# IOBR.net
KiCad netlist of a schematic drawn in EAGLE
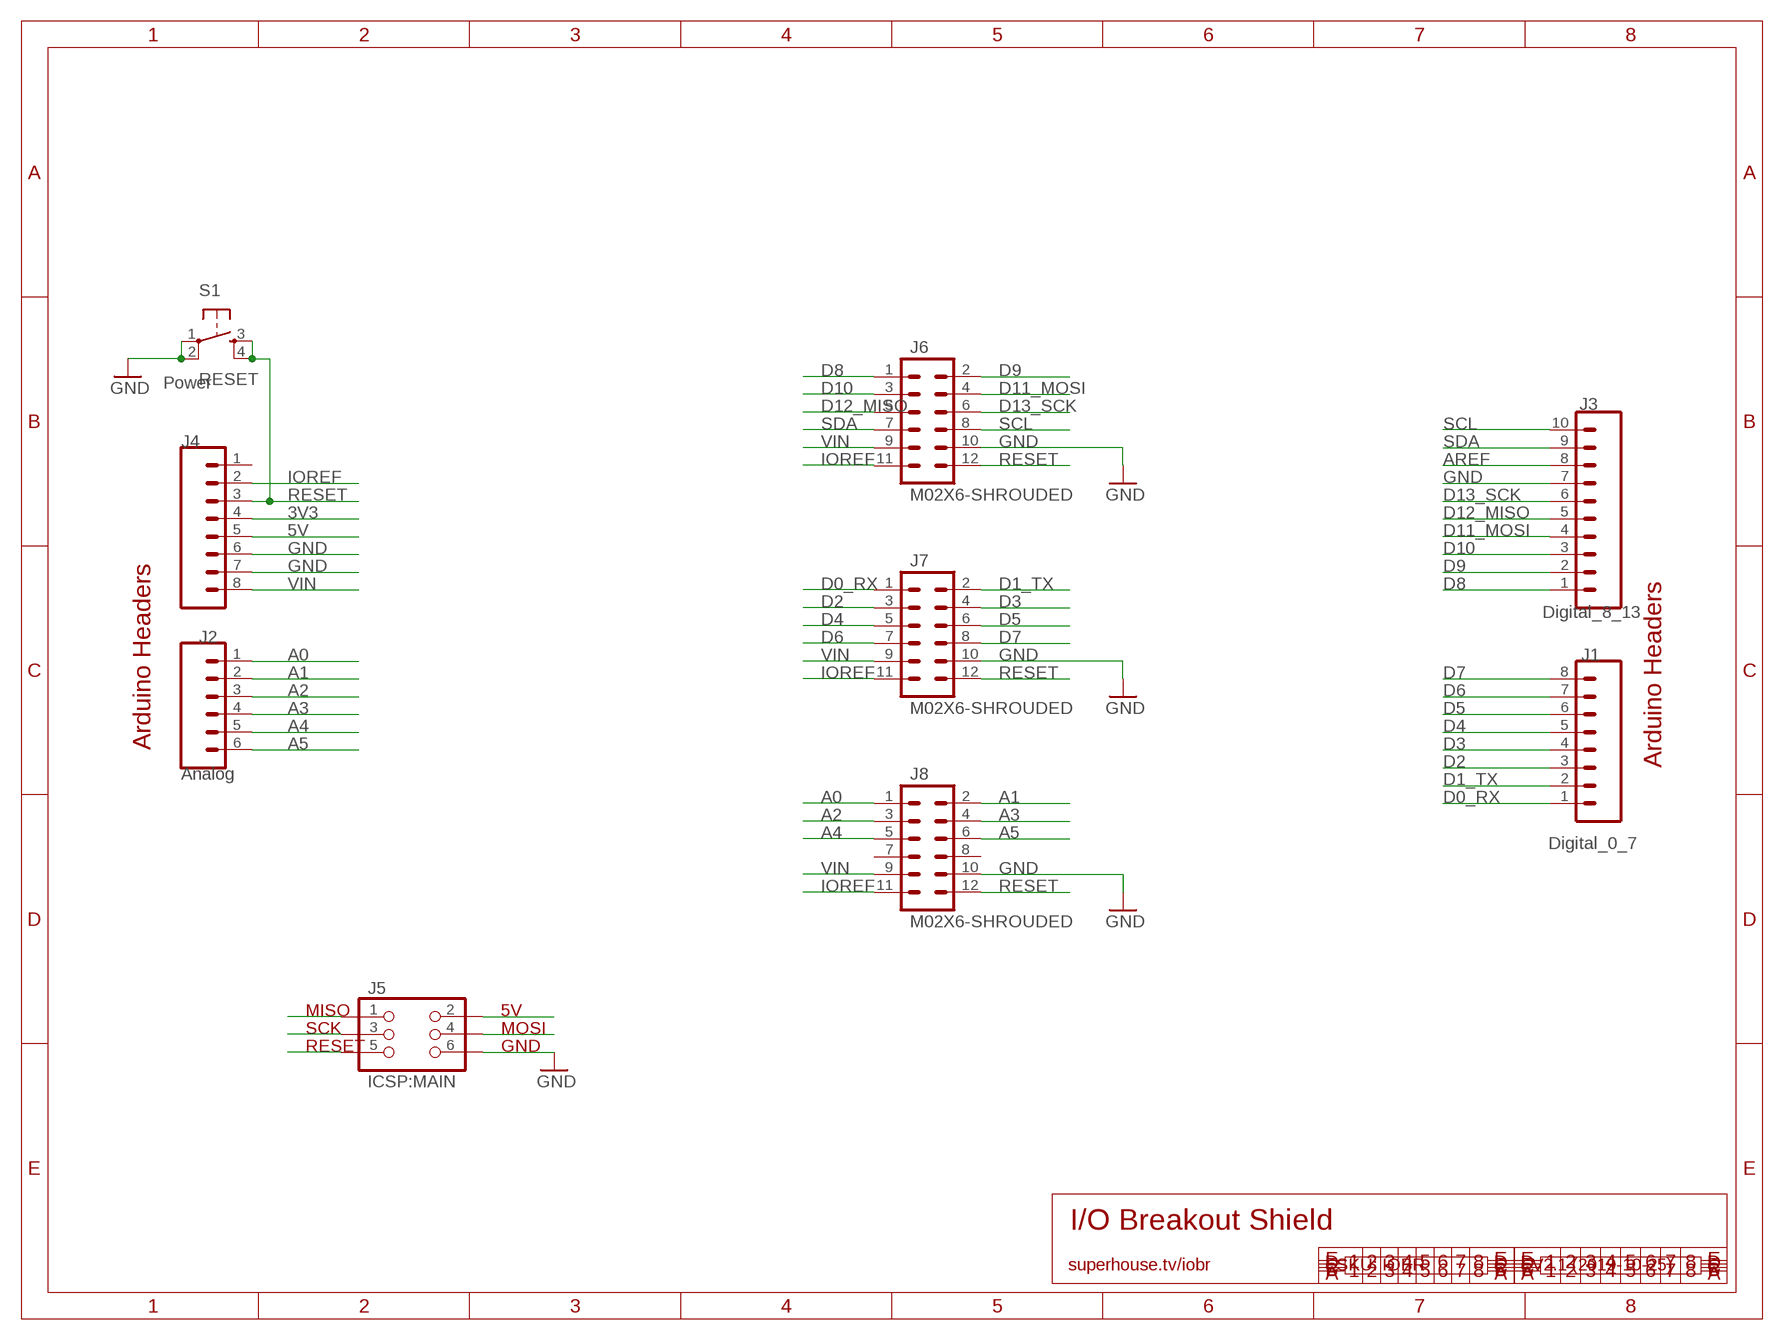
[diagram p0: schematic, sheet 1]

(export (version "E")
  (design (tool "Eeschema 10.0.6"))
  (components
    (comp (ref "J1")
      (value "Digital_0_7")
      (footprint "eagle-import:1X08-P-BELOW")
      (libsource (lib "eagle-import") (part "M08-PIN-BELOW"))
    )
    (comp (ref "J2")
      (value "Analog")
      (footprint "eagle-import:1X06-P-BELOW")
      (libsource (lib "eagle-import") (part "M06-PIN-BELOW"))
    )
    (comp (ref "J3")
      (value "Digital_8_13")
      (footprint "eagle-import:1X10-P-BELOW")
      (libsource (lib "eagle-import") (part "M10-PIN-BELOW"))
    )
    (comp (ref "J4")
      (value "Power")
      (footprint "eagle-import:1X08-P-BELOW")
      (libsource (lib "eagle-import") (part "M08-PIN-BELOW"))
    )
    (comp (ref "J5")
      (value "ICSP:MAIN")
      (footprint "eagle-import:2X03-ICSP-ST-BELOW")
      (libsource (lib "eagle-import") (part "ICSP-ST-BELOW"))
    )
    (comp (ref "J6")
      (value "M02X6-SHROUDED")
      (footprint "eagle-import:2X06-SHROUDED")
      (libsource (lib "eagle-import") (part "M02X6-SHROUDED"))
    )
    (comp (ref "J7")
      (value "M02X6-SHROUDED")
      (footprint "eagle-import:2X06-SHROUDED")
      (libsource (lib "eagle-import") (part "M02X6-SHROUDED"))
    )
    (comp (ref "J8")
      (value "M02X6-SHROUDED")
      (footprint "eagle-import:2X06-SHROUDED")
      (libsource (lib "eagle-import") (part "M02X6-SHROUDED"))
    )
    (comp (ref "S1")
      (value "RESET")
      (footprint "eagle-import:TACTILE-PTH-6MM")
      (libsource (lib "eagle-import") (part "TAC_SWITCH-PTH-6"))
    )
  )
  (nets
    (net (code "1") (name "/3V3") (class "Default")
      (node (ref "J4") (pin "4") (pinfunction "4_4") (pintype "passive"))
    )
    (net (code "2") (name "/5V") (class "Default")
      (node (ref "J4") (pin "5") (pinfunction "5_5") (pintype "passive"))
    )
    (net (code "3") (name "/A0") (class "Default")
      (node (ref "J2") (pin "1") (pinfunction "1_1") (pintype "passive"))
      (node (ref "J8") (pin "1") (pinfunction "1_1") (pintype "passive"))
    )
    (net (code "4") (name "/A1") (class "Default")
      (node (ref "J2") (pin "2") (pinfunction "2_2") (pintype "passive"))
      (node (ref "J8") (pin "2") (pinfunction "2_2") (pintype "passive"))
    )
    (net (code "5") (name "/A2") (class "Default")
      (node (ref "J2") (pin "3") (pinfunction "3_3") (pintype "passive"))
      (node (ref "J8") (pin "3") (pinfunction "3_3") (pintype "passive"))
    )
    (net (code "6") (name "/A3") (class "Default")
      (node (ref "J2") (pin "4") (pinfunction "4_4") (pintype "passive"))
      (node (ref "J8") (pin "4") (pinfunction "4_4") (pintype "passive"))
    )
    (net (code "7") (name "/A4") (class "Default")
      (node (ref "J2") (pin "5") (pinfunction "5_5") (pintype "passive"))
      (node (ref "J8") (pin "5") (pinfunction "5_5") (pintype "passive"))
    )
    (net (code "8") (name "/A5") (class "Default")
      (node (ref "J2") (pin "6") (pinfunction "6_6") (pintype "passive"))
      (node (ref "J8") (pin "6") (pinfunction "6_6") (pintype "passive"))
    )
    (net (code "9") (name "/AREF") (class "Default")
      (node (ref "J3") (pin "8") (pinfunction "8_8") (pintype "passive"))
    )
    (net (code "10") (name "/D0_RX") (class "Default")
      (node (ref "J1") (pin "1") (pinfunction "1_1") (pintype "passive"))
      (node (ref "J7") (pin "1") (pinfunction "1_1") (pintype "passive"))
    )
    (net (code "11") (name "/D1_TX") (class "Default")
      (node (ref "J1") (pin "2") (pinfunction "2_2") (pintype "passive"))
      (node (ref "J7") (pin "2") (pinfunction "2_2") (pintype "passive"))
    )
    (net (code "12") (name "/D2") (class "Default")
      (node (ref "J1") (pin "3") (pinfunction "3_3") (pintype "passive"))
      (node (ref "J7") (pin "3") (pinfunction "3_3") (pintype "passive"))
    )
    (net (code "13") (name "/D3") (class "Default")
      (node (ref "J1") (pin "4") (pinfunction "4_4") (pintype "passive"))
      (node (ref "J7") (pin "4") (pinfunction "4_4") (pintype "passive"))
    )
    (net (code "14") (name "/D4") (class "Default")
      (node (ref "J1") (pin "5") (pinfunction "5_5") (pintype "passive"))
      (node (ref "J7") (pin "5") (pinfunction "5_5") (pintype "passive"))
    )
    (net (code "15") (name "/D5") (class "Default")
      (node (ref "J1") (pin "6") (pinfunction "6_6") (pintype "passive"))
      (node (ref "J7") (pin "6") (pinfunction "6_6") (pintype "passive"))
    )
    (net (code "16") (name "/D6") (class "Default")
      (node (ref "J1") (pin "7") (pinfunction "7_7") (pintype "passive"))
      (node (ref "J7") (pin "7") (pinfunction "7_7") (pintype "passive"))
    )
    (net (code "17") (name "/D7") (class "Default")
      (node (ref "J1") (pin "8") (pinfunction "8_8") (pintype "passive"))
      (node (ref "J7") (pin "8") (pinfunction "8_8") (pintype "passive"))
    )
    (net (code "18") (name "/D8") (class "Default")
      (node (ref "J3") (pin "1") (pinfunction "1_1") (pintype "passive"))
      (node (ref "J6") (pin "1") (pinfunction "1_1") (pintype "passive"))
    )
    (net (code "19") (name "/D9") (class "Default")
      (node (ref "J3") (pin "2") (pinfunction "2_2") (pintype "passive"))
      (node (ref "J6") (pin "2") (pinfunction "2_2") (pintype "passive"))
    )
    (net (code "20") (name "/D10") (class "Default")
      (node (ref "J3") (pin "3") (pinfunction "3_3") (pintype "passive"))
      (node (ref "J6") (pin "3") (pinfunction "3_3") (pintype "passive"))
    )
    (net (code "21") (name "/D11_MOSI") (class "Default")
      (node (ref "J3") (pin "4") (pinfunction "4_4") (pintype "passive"))
      (node (ref "J6") (pin "4") (pinfunction "4_4") (pintype "passive"))
    )
    (net (code "22") (name "/D12_MISO") (class "Default")
      (node (ref "J3") (pin "5") (pinfunction "5_5") (pintype "passive"))
      (node (ref "J6") (pin "5") (pinfunction "5_5") (pintype "passive"))
    )
    (net (code "23") (name "/D13_SCK") (class "Default")
      (node (ref "J3") (pin "6") (pinfunction "6_6") (pintype "passive"))
      (node (ref "J6") (pin "6") (pinfunction "6_6") (pintype "passive"))
    )
    (net (code "24") (name "/IOREF") (class "Default")
      (node (ref "J4") (pin "2") (pinfunction "2_2") (pintype "passive"))
      (node (ref "J6") (pin "11") (pinfunction "11_11") (pintype "passive"))
      (node (ref "J7") (pin "11") (pinfunction "11_11") (pintype "passive"))
      (node (ref "J8") (pin "11") (pinfunction "11_11") (pintype "passive"))
    )
    (net (code "25") (name "/RESET") (class "Default")
      (node (ref "J4") (pin "3") (pinfunction "3_3") (pintype "passive"))
      (node (ref "J6") (pin "12") (pinfunction "12_12") (pintype "passive"))
      (node (ref "J7") (pin "12") (pinfunction "12_12") (pintype "passive"))
      (node (ref "J8") (pin "12") (pinfunction "12_12") (pintype "passive"))
      (node (ref "S1") (pin "3") (pinfunction "3_3") (pintype "passive"))
      (node (ref "S1") (pin "4") (pinfunction "4_4") (pintype "passive"))
    )
    (net (code "26") (name "/SCL") (class "Default")
      (node (ref "J3") (pin "10") (pinfunction "10_10") (pintype "passive"))
      (node (ref "J6") (pin "8") (pinfunction "8_8") (pintype "passive"))
    )
    (net (code "27") (name "/SDA") (class "Default")
      (node (ref "J3") (pin "9") (pinfunction "9_9") (pintype "passive"))
      (node (ref "J6") (pin "7") (pinfunction "7_7") (pintype "passive"))
    )
    (net (code "28") (name "/VIN") (class "Default")
      (node (ref "J4") (pin "8") (pinfunction "8_8") (pintype "passive"))
      (node (ref "J6") (pin "9") (pinfunction "9_9") (pintype "passive"))
      (node (ref "J7") (pin "9") (pinfunction "9_9") (pintype "passive"))
      (node (ref "J8") (pin "9") (pinfunction "9_9") (pintype "passive"))
    )
    (net (code "29") (name "GND") (class "Default")
      (node (ref "J3") (pin "7") (pinfunction "7_7") (pintype "passive"))
      (node (ref "J4") (pin "6") (pinfunction "6_6") (pintype "passive"))
      (node (ref "J4") (pin "7") (pinfunction "7_7") (pintype "passive"))
      (node (ref "J5") (pin "6") (pinfunction "6_6") (pintype "passive"))
      (node (ref "J6") (pin "10") (pinfunction "10_10") (pintype "passive"))
      (node (ref "J7") (pin "10") (pinfunction "10_10") (pintype "passive"))
      (node (ref "J8") (pin "10") (pinfunction "10_10") (pintype "passive"))
      (node (ref "S1") (pin "1") (pinfunction "1_1") (pintype "passive"))
      (node (ref "S1") (pin "2") (pinfunction "2_2") (pintype "passive"))
    )
    (net (code "30") (name "unconnected-(J4-Pad1)") (class "Default")
      (node (ref "J4") (pin "1") (pinfunction "1_1") (pintype "passive"))
    )
    (net (code "31") (name "unconnected-(J5-Pad1)") (class "Default")
      (node (ref "J5") (pin "1") (pinfunction "1_1") (pintype "passive"))
    )
    (net (code "32") (name "unconnected-(J5-Pad2)") (class "Default")
      (node (ref "J5") (pin "2") (pinfunction "2_2") (pintype "passive"))
    )
    (net (code "33") (name "unconnected-(J5-Pad3)") (class "Default")
      (node (ref "J5") (pin "3") (pinfunction "3_3") (pintype "passive"))
    )
    (net (code "34") (name "unconnected-(J5-Pad4)") (class "Default")
      (node (ref "J5") (pin "4") (pinfunction "4_4") (pintype "passive"))
    )
    (net (code "35") (name "unconnected-(J5-Pad5)") (class "Default")
      (node (ref "J5") (pin "5") (pinfunction "5_5") (pintype "passive"))
    )
    (net (code "36") (name "unconnected-(J8-Pad7)") (class "Default")
      (node (ref "J8") (pin "7") (pinfunction "7_7") (pintype "passive"))
    )
    (net (code "37") (name "unconnected-(J8-Pad8)") (class "Default")
      (node (ref "J8") (pin "8") (pinfunction "8_8") (pintype "passive"))
    )
  )
)
